# 4-HCloverMedallion.net
KiCad netlist of a schematic drawn in EAGLE
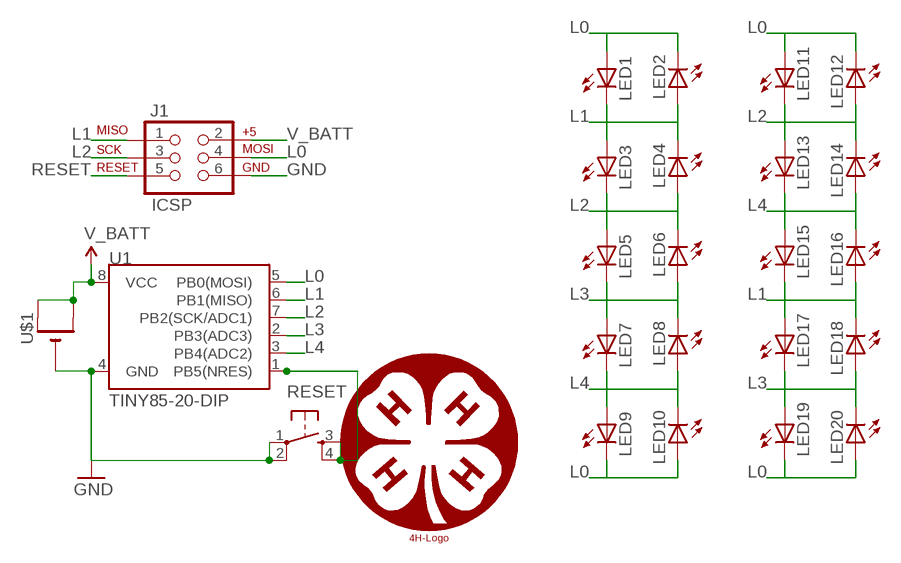
[diagram p0: schematic, sheet 1]

(export (version "E")
  (design (tool "Eeschema 10.0.6"))
  (components
    (comp (ref "J1")
      (value "ICSP")
      (footprint "eagle-import:2X3-NS")
      (libsource (lib "eagle-import") (part "AVR_SPI_PRG_6LABELED"))
    )
    (comp (ref "LED1")
      (value "LED5MM")
      (footprint "eagle-import:LED5MM")
      (libsource (lib "eagle-import") (part "LED5MM"))
    )
    (comp (ref "LED2")
      (value "LED5MM")
      (footprint "eagle-import:LED5MM")
      (libsource (lib "eagle-import") (part "LED5MM"))
    )
    (comp (ref "LED3")
      (value "LED5MM")
      (footprint "eagle-import:LED5MM")
      (libsource (lib "eagle-import") (part "LED5MM"))
    )
    (comp (ref "LED4")
      (value "LED5MM")
      (footprint "eagle-import:LED5MM")
      (libsource (lib "eagle-import") (part "LED5MM"))
    )
    (comp (ref "LED5")
      (value "LED5MM")
      (footprint "eagle-import:LED5MM")
      (libsource (lib "eagle-import") (part "LED5MM"))
    )
    (comp (ref "LED6")
      (value "LED5MM")
      (footprint "eagle-import:LED5MM")
      (libsource (lib "eagle-import") (part "LED5MM"))
    )
    (comp (ref "LED7")
      (value "LED5MM")
      (footprint "eagle-import:LED5MM")
      (libsource (lib "eagle-import") (part "LED5MM"))
    )
    (comp (ref "LED8")
      (value "LED5MM")
      (footprint "eagle-import:LED5MM")
      (libsource (lib "eagle-import") (part "LED5MM"))
    )
    (comp (ref "LED9")
      (value "LED5MM")
      (footprint "eagle-import:LED5MM")
      (libsource (lib "eagle-import") (part "LED5MM"))
    )
    (comp (ref "LED10")
      (value "LED5MM")
      (footprint "eagle-import:LED5MM")
      (libsource (lib "eagle-import") (part "LED5MM"))
    )
    (comp (ref "LED11")
      (value "LED5MM")
      (footprint "eagle-import:LED5MM")
      (libsource (lib "eagle-import") (part "LED5MM"))
    )
    (comp (ref "LED12")
      (value "LED5MM")
      (footprint "eagle-import:LED5MM")
      (libsource (lib "eagle-import") (part "LED5MM"))
    )
    (comp (ref "LED13")
      (value "LED5MM")
      (footprint "eagle-import:LED5MM")
      (libsource (lib "eagle-import") (part "LED5MM"))
    )
    (comp (ref "LED14")
      (value "LED5MM")
      (footprint "eagle-import:LED5MM")
      (libsource (lib "eagle-import") (part "LED5MM"))
    )
    (comp (ref "LED15")
      (value "LED5MM")
      (footprint "eagle-import:LED5MM")
      (libsource (lib "eagle-import") (part "LED5MM"))
    )
    (comp (ref "LED16")
      (value "LED5MM")
      (footprint "eagle-import:LED5MM")
      (libsource (lib "eagle-import") (part "LED5MM"))
    )
    (comp (ref "LED17")
      (value "LED5MM")
      (footprint "eagle-import:LED5MM")
      (libsource (lib "eagle-import") (part "LED5MM"))
    )
    (comp (ref "LED18")
      (value "LED5MM")
      (footprint "eagle-import:LED5MM")
      (libsource (lib "eagle-import") (part "LED5MM"))
    )
    (comp (ref "LED19")
      (value "LED5MM")
      (footprint "eagle-import:LED5MM")
      (libsource (lib "eagle-import") (part "LED5MM"))
    )
    (comp (ref "LED20")
      (value "LED5MM")
      (footprint "eagle-import:LED5MM")
      (libsource (lib "eagle-import") (part "LED5MM"))
    )
    (comp (ref "RESET")
      (value "TAC_SWITCHPTH")
      (footprint "eagle-import:TACTILE-PTH")
      (libsource (lib "eagle-import") (part "TAC_SWITCHPTH"))
    )
    (comp (ref "U$1")
      (value "CR2032THM")
      (footprint "eagle-import:CR2032-THRU")
      (libsource (lib "eagle-import") (part "CR2032THM"))
    )
    (comp (ref "U$2")
      (value "4H-LOGO14")
      (footprint "eagle-import:4H_LOGO_14")
      (libsource (lib "eagle-import") (part "4H-LOGO14"))
    )
    (comp (ref "U1")
      (value "TINY85-20-DIP")
      (footprint "eagle-import:DIP08")
      (libsource (lib "eagle-import") (part "ATTINY45TINY85-20-DIP"))
    )
  )
  (nets
    (net (code "1") (name "/L0") (class "Default")
      (node (ref "J1") (pin "4") (pinfunction "MOSI_4") (pintype "passive"))
      (node (ref "LED1") (pin "A") (pinfunction "A_A") (pintype "passive"))
      (node (ref "LED10") (pin "A") (pinfunction "A_A") (pintype "passive"))
      (node (ref "LED11") (pin "A") (pinfunction "A_A") (pintype "passive"))
      (node (ref "LED12") (pin "K") (pinfunction "C_K") (pintype "passive"))
      (node (ref "LED19") (pin "K") (pinfunction "C_K") (pintype "passive"))
      (node (ref "LED2") (pin "K") (pinfunction "C_K") (pintype "passive"))
      (node (ref "LED20") (pin "A") (pinfunction "A_A") (pintype "passive"))
      (node (ref "LED9") (pin "K") (pinfunction "C_K") (pintype "passive"))
      (node (ref "U1") (pin "5") (pinfunction "PB0(MOSI)_5") (pintype "bidirectional"))
    )
    (net (code "2") (name "/L1") (class "Default")
      (node (ref "J1") (pin "1") (pinfunction "MISO_1") (pintype "passive"))
      (node (ref "LED1") (pin "K") (pinfunction "C_K") (pintype "passive"))
      (node (ref "LED15") (pin "K") (pinfunction "C_K") (pintype "passive"))
      (node (ref "LED16") (pin "A") (pinfunction "A_A") (pintype "passive"))
      (node (ref "LED17") (pin "A") (pinfunction "A_A") (pintype "passive"))
      (node (ref "LED18") (pin "K") (pinfunction "C_K") (pintype "passive"))
      (node (ref "LED2") (pin "A") (pinfunction "A_A") (pintype "passive"))
      (node (ref "LED3") (pin "A") (pinfunction "A_A") (pintype "passive"))
      (node (ref "LED4") (pin "K") (pinfunction "C_K") (pintype "passive"))
      (node (ref "U1") (pin "6") (pinfunction "PB1(MISO)_6") (pintype "bidirectional"))
    )
    (net (code "3") (name "/L2") (class "Default")
      (node (ref "J1") (pin "3") (pinfunction "SCK_3") (pintype "passive"))
      (node (ref "LED11") (pin "K") (pinfunction "C_K") (pintype "passive"))
      (node (ref "LED12") (pin "A") (pinfunction "A_A") (pintype "passive"))
      (node (ref "LED13") (pin "A") (pinfunction "A_A") (pintype "passive"))
      (node (ref "LED14") (pin "K") (pinfunction "C_K") (pintype "passive"))
      (node (ref "LED3") (pin "K") (pinfunction "C_K") (pintype "passive"))
      (node (ref "LED4") (pin "A") (pinfunction "A_A") (pintype "passive"))
      (node (ref "LED5") (pin "A") (pinfunction "A_A") (pintype "passive"))
      (node (ref "LED6") (pin "K") (pinfunction "C_K") (pintype "passive"))
      (node (ref "U1") (pin "7") (pinfunction "PB2(SCK/ADC1)_7") (pintype "bidirectional"))
    )
    (net (code "4") (name "/L3") (class "Default")
      (node (ref "LED17") (pin "K") (pinfunction "C_K") (pintype "passive"))
      (node (ref "LED18") (pin "A") (pinfunction "A_A") (pintype "passive"))
      (node (ref "LED19") (pin "A") (pinfunction "A_A") (pintype "passive"))
      (node (ref "LED20") (pin "K") (pinfunction "C_K") (pintype "passive"))
      (node (ref "LED5") (pin "K") (pinfunction "C_K") (pintype "passive"))
      (node (ref "LED6") (pin "A") (pinfunction "A_A") (pintype "passive"))
      (node (ref "LED7") (pin "A") (pinfunction "A_A") (pintype "passive"))
      (node (ref "LED8") (pin "K") (pinfunction "C_K") (pintype "passive"))
      (node (ref "U1") (pin "2") (pinfunction "PB3(ADC3)_2") (pintype "bidirectional"))
    )
    (net (code "5") (name "/L4") (class "Default")
      (node (ref "LED10") (pin "K") (pinfunction "C_K") (pintype "passive"))
      (node (ref "LED13") (pin "K") (pinfunction "C_K") (pintype "passive"))
      (node (ref "LED14") (pin "A") (pinfunction "A_A") (pintype "passive"))
      (node (ref "LED15") (pin "A") (pinfunction "A_A") (pintype "passive"))
      (node (ref "LED16") (pin "K") (pinfunction "C_K") (pintype "passive"))
      (node (ref "LED7") (pin "K") (pinfunction "C_K") (pintype "passive"))
      (node (ref "LED8") (pin "A") (pinfunction "A_A") (pintype "passive"))
      (node (ref "LED9") (pin "A") (pinfunction "A_A") (pintype "passive"))
      (node (ref "U1") (pin "3") (pinfunction "PB4(ADC2)_3") (pintype "bidirectional"))
    )
    (net (code "6") (name "/RESET") (class "Default")
      (node (ref "J1") (pin "5") (pinfunction "RST_5") (pintype "passive"))
      (node (ref "RESET") (pin "3") (pinfunction "3_3") (pintype "passive"))
      (node (ref "RESET") (pin "4") (pinfunction "4_4") (pintype "passive"))
      (node (ref "U1") (pin "1") (pinfunction "PB5(NRES)_1") (pintype "bidirectional"))
    )
    (net (code "7") (name "GND") (class "Default")
      (node (ref "J1") (pin "6") (pinfunction "GND_6") (pintype "passive"))
      (node (ref "RESET") (pin "1") (pinfunction "1_1") (pintype "passive"))
      (node (ref "RESET") (pin "2") (pinfunction "2_2") (pintype "passive"))
      (node (ref "U$1") (pin "-") (pinfunction "-_-") (pintype "passive"))
      (node (ref "U1") (pin "4") (pinfunction "GND_4") (pintype "bidirectional"))
    )
    (net (code "8") (name "V_BATT") (class "Default")
      (node (ref "J1") (pin "2") (pinfunction "V+_2") (pintype "passive"))
      (node (ref "U$1") (pin "+1") (pinfunction "+_+1") (pintype "passive"))
      (node (ref "U$1") (pin "+2") (pinfunction "+1_+2") (pintype "passive"))
      (node (ref "U1") (pin "8") (pinfunction "VCC_8") (pintype "bidirectional"))
    )
  )
)
